# right_board.net
KiCad netlist of a schematic drawn in EAGLE
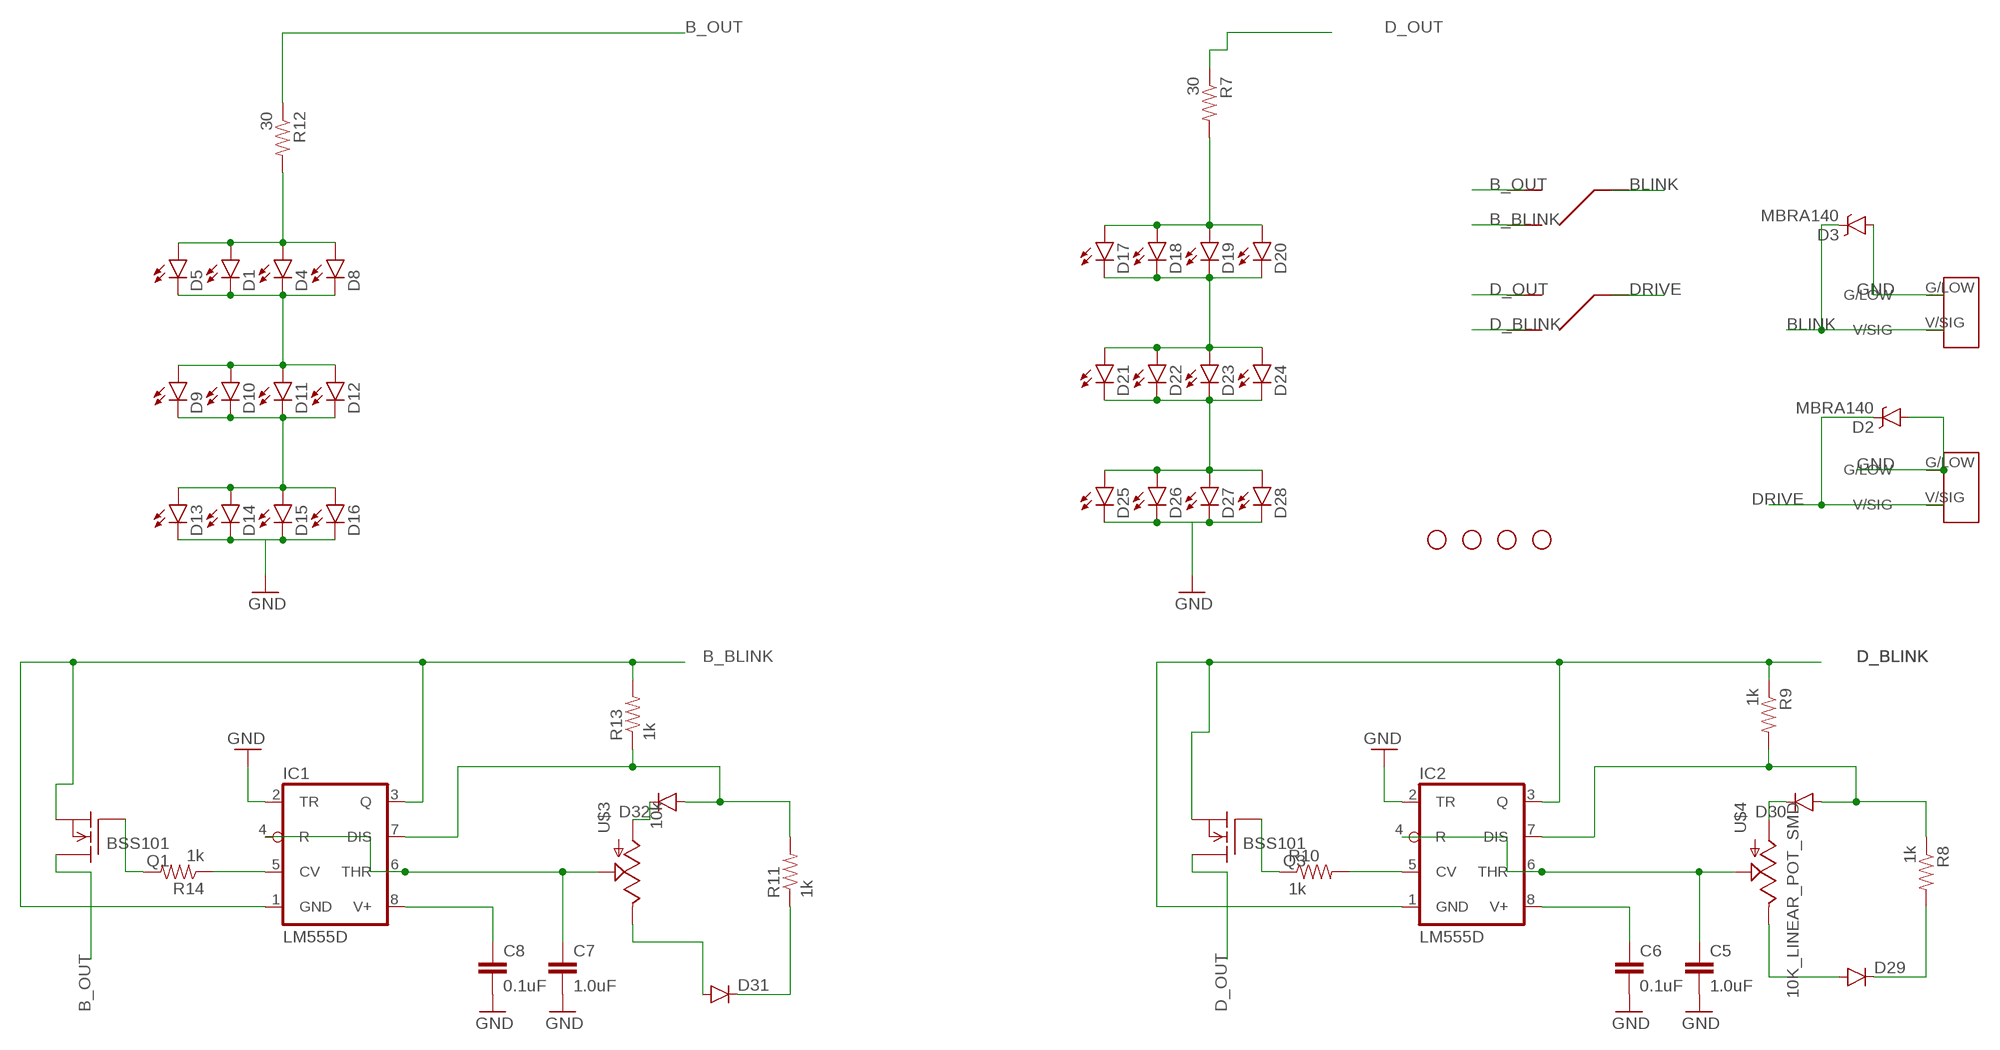
[diagram p0: schematic, sheet 1]

(export (version "E")
  (design (tool "Eeschema 10.0.6"))
  (components
    (comp (ref "C5")
      (value "1.0uF")
      (footprint "eagle-import:0805-CAP")
      (libsource (lib "eagle-import") (part "1.0UF-25V-+80/-20(0805){dblquote}"))
    )
    (comp (ref "C6")
      (value "0.1uF")
      (footprint "eagle-import:0603-CAP")
      (libsource (lib "eagle-import") (part "0.1UF-25V(+80/-20%)(0603)"))
    )
    (comp (ref "C7")
      (value "1.0uF")
      (footprint "eagle-import:0805-CAP")
      (libsource (lib "eagle-import") (part "1.0UF-25V-+80/-20(0805){dblquote}"))
    )
    (comp (ref "C8")
      (value "0.1uF")
      (footprint "eagle-import:0603-CAP")
      (libsource (lib "eagle-import") (part "0.1UF-25V(+80/-20%)(0603)"))
    )
    (comp (ref "D1")
      (value "LED5MM")
      (footprint "eagle-import:LED5MM")
      (libsource (lib "eagle-import") (part "LED5MM"))
    )
    (comp (ref "D2")
      (value "MBRA140")
      (footprint "eagle-import:SMA-DIODE")
      (libsource (lib "eagle-import") (part "MBRA140"))
    )
    (comp (ref "D3")
      (value "MBRA140")
      (footprint "eagle-import:SMA-DIODE")
      (libsource (lib "eagle-import") (part "MBRA140"))
    )
    (comp (ref "D4")
      (value "LED5MM")
      (footprint "eagle-import:LED5MM")
      (libsource (lib "eagle-import") (part "LED5MM"))
    )
    (comp (ref "D5")
      (value "LED5MM")
      (footprint "eagle-import:LED5MM")
      (libsource (lib "eagle-import") (part "LED5MM"))
    )
    (comp (ref "D8")
      (value "LED5MM")
      (footprint "eagle-import:LED5MM")
      (libsource (lib "eagle-import") (part "LED5MM"))
    )
    (comp (ref "D9")
      (value "LED5MM")
      (footprint "eagle-import:LED5MM")
      (libsource (lib "eagle-import") (part "LED5MM"))
    )
    (comp (ref "D10")
      (value "LED5MM")
      (footprint "eagle-import:LED5MM")
      (libsource (lib "eagle-import") (part "LED5MM"))
    )
    (comp (ref "D11")
      (value "LED5MM")
      (footprint "eagle-import:LED5MM")
      (libsource (lib "eagle-import") (part "LED5MM"))
    )
    (comp (ref "D12")
      (value "LED5MM")
      (footprint "eagle-import:LED5MM")
      (libsource (lib "eagle-import") (part "LED5MM"))
    )
    (comp (ref "D13")
      (value "LED5MM")
      (footprint "eagle-import:LED5MM")
      (libsource (lib "eagle-import") (part "LED5MM"))
    )
    (comp (ref "D14")
      (value "LED5MM")
      (footprint "eagle-import:LED5MM")
      (libsource (lib "eagle-import") (part "LED5MM"))
    )
    (comp (ref "D15")
      (value "LED5MM")
      (footprint "eagle-import:LED5MM")
      (libsource (lib "eagle-import") (part "LED5MM"))
    )
    (comp (ref "D16")
      (value "LED5MM")
      (footprint "eagle-import:LED5MM")
      (libsource (lib "eagle-import") (part "LED5MM"))
    )
    (comp (ref "D17")
      (value "LED5MM")
      (footprint "eagle-import:LED5MM")
      (libsource (lib "eagle-import") (part "LED5MM"))
    )
    (comp (ref "D18")
      (value "LED5MM")
      (footprint "eagle-import:LED5MM")
      (libsource (lib "eagle-import") (part "LED5MM"))
    )
    (comp (ref "D19")
      (value "LED5MM")
      (footprint "eagle-import:LED5MM")
      (libsource (lib "eagle-import") (part "LED5MM"))
    )
    (comp (ref "D20")
      (value "LED5MM")
      (footprint "eagle-import:LED5MM")
      (libsource (lib "eagle-import") (part "LED5MM"))
    )
    (comp (ref "D21")
      (value "LED5MM")
      (footprint "eagle-import:LED5MM")
      (libsource (lib "eagle-import") (part "LED5MM"))
    )
    (comp (ref "D22")
      (value "LED5MM")
      (footprint "eagle-import:LED5MM")
      (libsource (lib "eagle-import") (part "LED5MM"))
    )
    (comp (ref "D23")
      (value "LED5MM")
      (footprint "eagle-import:LED5MM")
      (libsource (lib "eagle-import") (part "LED5MM"))
    )
    (comp (ref "D24")
      (value "LED5MM")
      (footprint "eagle-import:LED5MM")
      (libsource (lib "eagle-import") (part "LED5MM"))
    )
    (comp (ref "D25")
      (value "LED5MM")
      (footprint "eagle-import:LED5MM")
      (libsource (lib "eagle-import") (part "LED5MM"))
    )
    (comp (ref "D26")
      (value "LED5MM")
      (footprint "eagle-import:LED5MM")
      (libsource (lib "eagle-import") (part "LED5MM"))
    )
    (comp (ref "D27")
      (value "LED5MM")
      (footprint "eagle-import:LED5MM")
      (libsource (lib "eagle-import") (part "LED5MM"))
    )
    (comp (ref "D28")
      (value "LED5MM")
      (footprint "eagle-import:LED5MM")
      (libsource (lib "eagle-import") (part "LED5MM"))
    )
    (comp (ref "D29")
      (value "DIODESMA")
      (footprint "eagle-import:SMA-DIODE")
      (libsource (lib "eagle-import") (part "DIODESMA"))
    )
    (comp (ref "D30")
      (value "DIODESMA")
      (footprint "eagle-import:SMA-DIODE")
      (libsource (lib "eagle-import") (part "DIODESMA"))
    )
    (comp (ref "D31")
      (value "DIODESMA")
      (footprint "eagle-import:SMA-DIODE")
      (libsource (lib "eagle-import") (part "DIODESMA"))
    )
    (comp (ref "D32")
      (value "DIODESMA")
      (footprint "eagle-import:SMA-DIODE")
      (libsource (lib "eagle-import") (part "DIODESMA"))
    )
    (comp (ref "H1")
      (value "STAND-OFF")
      (footprint "eagle-import:STAND-OFF")
      (libsource (lib "eagle-import") (part "STAND-OFF"))
    )
    (comp (ref "H2")
      (value "STAND-OFF")
      (footprint "eagle-import:STAND-OFF")
      (libsource (lib "eagle-import") (part "STAND-OFF"))
    )
    (comp (ref "H3")
      (value "STAND-OFF")
      (footprint "eagle-import:STAND-OFF")
      (libsource (lib "eagle-import") (part "STAND-OFF"))
    )
    (comp (ref "H4")
      (value "STAND-OFF")
      (footprint "eagle-import:STAND-OFF")
      (libsource (lib "eagle-import") (part "STAND-OFF"))
    )
    (comp (ref "IC1")
      (value "LM555D")
      (footprint "eagle-import:SO08")
      (libsource (lib "eagle-import") (part "555DLM"))
    )
    (comp (ref "IC2")
      (value "LM555D")
      (footprint "eagle-import:SO08")
      (libsource (lib "eagle-import") (part "555DLM"))
    )
    (comp (ref "Q1")
      (value "BSS101")
      (footprint "eagle-import:TO92")
      (libsource (lib "eagle-import") (part "BSS101"))
    )
    (comp (ref "Q3")
      (value "BSS101")
      (footprint "eagle-import:TO92")
      (libsource (lib "eagle-import") (part "BSS101"))
    )
    (comp (ref "R7")
      (value "30")
      (footprint "eagle-import:0805")
      (libsource (lib "eagle-import") (part "0.22OHM-1/4W-1%(0805)"))
    )
    (comp (ref "R8")
      (value "1k")
      (footprint "eagle-import:0805")
      (libsource (lib "eagle-import") (part "0.22OHM-1/4W-1%(0805)"))
    )
    (comp (ref "R9")
      (value "1k")
      (footprint "eagle-import:0805")
      (libsource (lib "eagle-import") (part "0.22OHM-1/4W-1%(0805)"))
    )
    (comp (ref "R10")
      (value "1k")
      (footprint "eagle-import:0805")
      (libsource (lib "eagle-import") (part "0.22OHM-1/4W-1%(0805)"))
    )
    (comp (ref "R11")
      (value "1k")
      (footprint "eagle-import:0805")
      (libsource (lib "eagle-import") (part "0.22OHM-1/4W-1%(0805)"))
    )
    (comp (ref "R12")
      (value "30")
      (footprint "eagle-import:0805")
      (libsource (lib "eagle-import") (part "0.22OHM-1/4W-1%(0805)"))
    )
    (comp (ref "R13")
      (value "1k")
      (footprint "eagle-import:0805")
      (libsource (lib "eagle-import") (part "0.22OHM-1/4W-1%(0805)"))
    )
    (comp (ref "R14")
      (value "1k")
      (footprint "eagle-import:0805")
      (libsource (lib "eagle-import") (part "0.22OHM-1/4W-1%(0805)"))
    )
    (comp (ref "U$1")
      (value "JS_SERIES_SLIDESWITCCH")
      (footprint "eagle-import:MYPART3")
      (libsource (lib "eagle-import") (part "JS_SERIES_SLIDESWITCCH"))
    )
    (comp (ref "U$2")
      (value "JS_SERIES_SLIDESWITCCH")
      (footprint "eagle-import:MYPART3")
      (libsource (lib "eagle-import") (part "JS_SERIES_SLIDESWITCCH"))
    )
    (comp (ref "U$3")
      (value "10k")
      (footprint "eagle-import:TC33X")
      (libsource (lib "eagle-import") (part "10K_LINEAR_POT_SMD"))
    )
    (comp (ref "U$4")
      (value "10K_LINEAR_POT_SMD")
      (footprint "eagle-import:TC33X")
      (libsource (lib "eagle-import") (part "10K_LINEAR_POT_SMD"))
    )
    (comp (ref "U$5")
      (value "2_PIN_TECONNECTOR")
      (footprint "eagle-import:2_PIN_CONNECT")
      (libsource (lib "eagle-import") (part "2_PIN_TECONNECTOR"))
    )
    (comp (ref "U$6")
      (value "2_PIN_TECONNECTOR")
      (footprint "eagle-import:2_PIN_CONNECT")
      (libsource (lib "eagle-import") (part "2_PIN_TECONNECTOR"))
    )
  )
  (nets
    (net (code "1") (name "/BLINK") (class "Default")
      (node (ref "D3") (pin "C") (pinfunction "C_C") (pintype "passive"))
      (node (ref "U$1") (pin "IN") (pinfunction "IN_IN") (pintype "bidirectional"))
      (node (ref "U$5") (pin "V/SIG") (pinfunction "V/SIG_V/SIG") (pintype "bidirectional"))
    )
    (net (code "2") (name "/B_BLINK") (class "Default")
      (node (ref "IC1") (pin "1") (pinfunction "GND_1") (pintype "power_in"))
      (node (ref "IC1") (pin "3") (pinfunction "Q_3") (pintype "output"))
      (node (ref "Q1") (pin "1") (pinfunction "S_1") (pintype "passive"))
      (node (ref "R13") (pin "2") (pinfunction "2_2") (pintype "passive"))
      (node (ref "U$1") (pin "OUT1") (pinfunction "OUT1_OUT1") (pintype "bidirectional"))
    )
    (net (code "3") (name "/B_OUT") (class "Default")
      (node (ref "Q1") (pin "3") (pinfunction "D_3") (pintype "passive"))
      (node (ref "R12") (pin "1") (pinfunction "1_1") (pintype "passive"))
      (node (ref "U$1") (pin "OUT2") (pinfunction "OUT2_OUT2") (pintype "bidirectional"))
    )
    (net (code "4") (name "/DRIVE") (class "Default")
      (node (ref "D2") (pin "C") (pinfunction "C_C") (pintype "passive"))
      (node (ref "U$2") (pin "IN") (pinfunction "IN_IN") (pintype "bidirectional"))
      (node (ref "U$6") (pin "V/SIG") (pinfunction "V/SIG_V/SIG") (pintype "bidirectional"))
    )
    (net (code "5") (name "/D_BLINK") (class "Default")
      (node (ref "IC2") (pin "1") (pinfunction "GND_1") (pintype "power_in"))
      (node (ref "IC2") (pin "3") (pinfunction "Q_3") (pintype "output"))
      (node (ref "Q3") (pin "1") (pinfunction "S_1") (pintype "passive"))
      (node (ref "R9") (pin "1") (pinfunction "1_1") (pintype "passive"))
      (node (ref "U$2") (pin "OUT1") (pinfunction "OUT1_OUT1") (pintype "bidirectional"))
    )
    (net (code "6") (name "/D_OUT") (class "Default")
      (node (ref "Q3") (pin "3") (pinfunction "D_3") (pintype "passive"))
      (node (ref "R7") (pin "1") (pinfunction "1_1") (pintype "passive"))
      (node (ref "U$2") (pin "OUT2") (pinfunction "OUT2_OUT2") (pintype "bidirectional"))
    )
    (net (code "7") (name "GND") (class "Default")
      (node (ref "C5") (pin "2") (pinfunction "2_2") (pintype "passive"))
      (node (ref "C6") (pin "2") (pinfunction "2_2") (pintype "passive"))
      (node (ref "C7") (pin "2") (pinfunction "2_2") (pintype "passive"))
      (node (ref "C8") (pin "2") (pinfunction "2_2") (pintype "passive"))
      (node (ref "D13") (pin "K") (pinfunction "C_K") (pintype "passive"))
      (node (ref "D14") (pin "K") (pinfunction "C_K") (pintype "passive"))
      (node (ref "D15") (pin "K") (pinfunction "C_K") (pintype "passive"))
      (node (ref "D16") (pin "K") (pinfunction "C_K") (pintype "passive"))
      (node (ref "D2") (pin "A") (pinfunction "A_A") (pintype "passive"))
      (node (ref "D25") (pin "K") (pinfunction "C_K") (pintype "passive"))
      (node (ref "D26") (pin "K") (pinfunction "C_K") (pintype "passive"))
      (node (ref "D27") (pin "K") (pinfunction "C_K") (pintype "passive"))
      (node (ref "D28") (pin "K") (pinfunction "C_K") (pintype "passive"))
      (node (ref "D3") (pin "A") (pinfunction "A_A") (pintype "passive"))
      (node (ref "IC1") (pin "2") (pinfunction "TR_2") (pintype "input"))
      (node (ref "IC2") (pin "2") (pinfunction "TR_2") (pintype "input"))
      (node (ref "U$5") (pin "G/LOW") (pinfunction "G/LOW_G/LOW") (pintype "bidirectional"))
      (node (ref "U$6") (pin "G/LOW") (pinfunction "G/LOW_G/LOW") (pintype "bidirectional"))
    )
    (net (code "8") (name "Net-(D1-C)") (class "Default")
      (node (ref "D1") (pin "K") (pinfunction "C_K") (pintype "passive"))
      (node (ref "D10") (pin "A") (pinfunction "A_A") (pintype "passive"))
      (node (ref "D11") (pin "A") (pinfunction "A_A") (pintype "passive"))
      (node (ref "D12") (pin "A") (pinfunction "A_A") (pintype "passive"))
      (node (ref "D4") (pin "K") (pinfunction "C_K") (pintype "passive"))
      (node (ref "D5") (pin "K") (pinfunction "C_K") (pintype "passive"))
      (node (ref "D8") (pin "K") (pinfunction "C_K") (pintype "passive"))
      (node (ref "D9") (pin "A") (pinfunction "A_A") (pintype "passive"))
    )
    (net (code "9") (name "Net-(D1-PadA)") (class "Default")
      (node (ref "D1") (pin "A") (pinfunction "A_A") (pintype "passive"))
      (node (ref "D4") (pin "A") (pinfunction "A_A") (pintype "passive"))
      (node (ref "D5") (pin "A") (pinfunction "A_A") (pintype "passive"))
      (node (ref "D8") (pin "A") (pinfunction "A_A") (pintype "passive"))
      (node (ref "R12") (pin "2") (pinfunction "2_2") (pintype "passive"))
    )
    (net (code "10") (name "Net-(D10-C)") (class "Default")
      (node (ref "D10") (pin "K") (pinfunction "C_K") (pintype "passive"))
      (node (ref "D11") (pin "K") (pinfunction "C_K") (pintype "passive"))
      (node (ref "D12") (pin "K") (pinfunction "C_K") (pintype "passive"))
      (node (ref "D13") (pin "A") (pinfunction "A_A") (pintype "passive"))
      (node (ref "D14") (pin "A") (pinfunction "A_A") (pintype "passive"))
      (node (ref "D15") (pin "A") (pinfunction "A_A") (pintype "passive"))
      (node (ref "D16") (pin "A") (pinfunction "A_A") (pintype "passive"))
      (node (ref "D9") (pin "K") (pinfunction "C_K") (pintype "passive"))
    )
    (net (code "11") (name "Net-(D17-C)") (class "Default")
      (node (ref "D17") (pin "K") (pinfunction "C_K") (pintype "passive"))
      (node (ref "D18") (pin "K") (pinfunction "C_K") (pintype "passive"))
      (node (ref "D19") (pin "K") (pinfunction "C_K") (pintype "passive"))
      (node (ref "D20") (pin "K") (pinfunction "C_K") (pintype "passive"))
      (node (ref "D21") (pin "A") (pinfunction "A_A") (pintype "passive"))
      (node (ref "D22") (pin "A") (pinfunction "A_A") (pintype "passive"))
      (node (ref "D23") (pin "A") (pinfunction "A_A") (pintype "passive"))
      (node (ref "D24") (pin "A") (pinfunction "A_A") (pintype "passive"))
    )
    (net (code "12") (name "Net-(D17-PadA)") (class "Default")
      (node (ref "D17") (pin "A") (pinfunction "A_A") (pintype "passive"))
      (node (ref "D18") (pin "A") (pinfunction "A_A") (pintype "passive"))
      (node (ref "D19") (pin "A") (pinfunction "A_A") (pintype "passive"))
      (node (ref "D20") (pin "A") (pinfunction "A_A") (pintype "passive"))
      (node (ref "R7") (pin "2") (pinfunction "2_2") (pintype "passive"))
    )
    (net (code "13") (name "Net-(D21-C)") (class "Default")
      (node (ref "D21") (pin "K") (pinfunction "C_K") (pintype "passive"))
      (node (ref "D22") (pin "K") (pinfunction "C_K") (pintype "passive"))
      (node (ref "D23") (pin "K") (pinfunction "C_K") (pintype "passive"))
      (node (ref "D24") (pin "K") (pinfunction "C_K") (pintype "passive"))
      (node (ref "D25") (pin "A") (pinfunction "A_A") (pintype "passive"))
      (node (ref "D26") (pin "A") (pinfunction "A_A") (pintype "passive"))
      (node (ref "D27") (pin "A") (pinfunction "A_A") (pintype "passive"))
      (node (ref "D28") (pin "A") (pinfunction "A_A") (pintype "passive"))
    )
    (net (code "14") (name "Net-(D29-PadC)") (class "Default")
      (node (ref "D29") (pin "C") (pinfunction "C_C") (pintype "passive"))
      (node (ref "R8") (pin "2") (pinfunction "2_2") (pintype "passive"))
    )
    (net (code "15") (name "Net-(D31-PadC)") (class "Default")
      (node (ref "D31") (pin "C") (pinfunction "C_C") (pintype "passive"))
      (node (ref "R11") (pin "1") (pinfunction "1_1") (pintype "passive"))
    )
    (net (code "16") (name "Net-(IC1-CV)") (class "Default")
      (node (ref "IC1") (pin "5") (pinfunction "CV_5") (pintype "input"))
      (node (ref "R14") (pin "1") (pinfunction "1_1") (pintype "passive"))
    )
    (net (code "17") (name "Net-(IC1-DIS)") (class "Default")
      (node (ref "D32") (pin "A") (pinfunction "A_A") (pintype "passive"))
      (node (ref "IC1") (pin "7") (pinfunction "DIS_7") (pintype "input"))
      (node (ref "R11") (pin "2") (pinfunction "2_2") (pintype "passive"))
      (node (ref "R13") (pin "1") (pinfunction "1_1") (pintype "passive"))
    )
    (net (code "18") (name "Net-(IC1-R)") (class "Default")
      (node (ref "C7") (pin "1") (pinfunction "1_1") (pintype "passive"))
      (node (ref "IC1") (pin "4") (pinfunction "R_4") (pintype "input"))
      (node (ref "IC1") (pin "6") (pinfunction "THR_6") (pintype "input"))
      (node (ref "U$3") (pin "2") (pinfunction "S_2") (pintype "passive"))
    )
    (net (code "19") (name "Net-(IC1-V+)") (class "Default")
      (node (ref "C8") (pin "1") (pinfunction "1_1") (pintype "passive"))
      (node (ref "IC1") (pin "8") (pinfunction "V+_8") (pintype "power_in"))
    )
    (net (code "20") (name "Net-(IC2-CV)") (class "Default")
      (node (ref "IC2") (pin "5") (pinfunction "CV_5") (pintype "input"))
      (node (ref "R10") (pin "2") (pinfunction "2_2") (pintype "passive"))
    )
    (net (code "21") (name "Net-(IC2-DIS)") (class "Default")
      (node (ref "D30") (pin "A") (pinfunction "A_A") (pintype "passive"))
      (node (ref "IC2") (pin "7") (pinfunction "DIS_7") (pintype "input"))
      (node (ref "R8") (pin "1") (pinfunction "1_1") (pintype "passive"))
      (node (ref "R9") (pin "2") (pinfunction "2_2") (pintype "passive"))
    )
    (net (code "22") (name "Net-(IC2-R)") (class "Default")
      (node (ref "C5") (pin "1") (pinfunction "1_1") (pintype "passive"))
      (node (ref "IC2") (pin "4") (pinfunction "R_4") (pintype "input"))
      (node (ref "IC2") (pin "6") (pinfunction "THR_6") (pintype "input"))
      (node (ref "U$4") (pin "2") (pinfunction "S_2") (pintype "passive"))
    )
    (net (code "23") (name "Net-(IC2-V+)") (class "Default")
      (node (ref "C6") (pin "1") (pinfunction "1_1") (pintype "passive"))
      (node (ref "IC2") (pin "8") (pinfunction "V+_8") (pintype "power_in"))
    )
    (net (code "24") (name "Net-(Q1-G)") (class "Default")
      (node (ref "Q1") (pin "2") (pinfunction "G_2") (pintype "passive"))
      (node (ref "R14") (pin "2") (pinfunction "2_2") (pintype "passive"))
    )
    (net (code "25") (name "Net-(Q3-G)") (class "Default")
      (node (ref "Q3") (pin "2") (pinfunction "G_2") (pintype "passive"))
      (node (ref "R10") (pin "1") (pinfunction "1_1") (pintype "passive"))
    )
    (net (code "26") (name "Net-(U$3-A)") (class "Default")
      (node (ref "D32") (pin "C") (pinfunction "C_C") (pintype "passive"))
      (node (ref "U$3") (pin "1") (pinfunction "A_1") (pintype "passive"))
    )
    (net (code "27") (name "Net-(U$3-E)") (class "Default")
      (node (ref "D31") (pin "A") (pinfunction "A_A") (pintype "passive"))
      (node (ref "U$3") (pin "3") (pinfunction "E_3") (pintype "passive"))
    )
    (net (code "28") (name "Net-(U$4-A)") (class "Default")
      (node (ref "D30") (pin "C") (pinfunction "C_C") (pintype "passive"))
      (node (ref "U$4") (pin "1") (pinfunction "A_1") (pintype "passive"))
    )
    (net (code "29") (name "Net-(U$4-E)") (class "Default")
      (node (ref "D29") (pin "A") (pinfunction "A_A") (pintype "passive"))
      (node (ref "U$4") (pin "3") (pinfunction "E_3") (pintype "passive"))
    )
  )
)
